# blinkers.net
KiCad netlist of a schematic drawn in Altium Designer
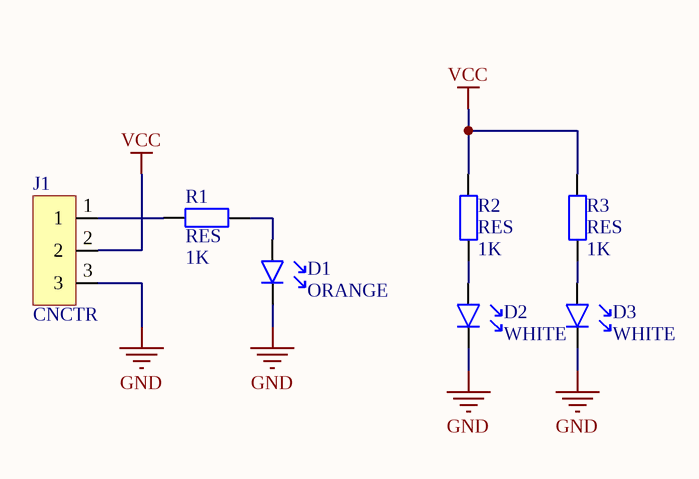
[diagram p0: blinkers.SchDoc]

(export (version "E")
  (design (tool "Eeschema 10.0.6"))
  (components
    (comp (ref "D1") (value "ORANGE") (footprint "RESC1608X06M") (libsource (lib "std") (part "LED")))
    (comp (ref "D2") (value "WHITE") (footprint "RESC1608X06M") (libsource (lib "std") (part "LED")))
    (comp (ref "D3") (value "WHITE") (footprint "RESC1608X06M") (libsource (lib "std") (part "LED")))
    (comp (ref "J1")
      (value "CNCTR")
      (footprint "CNCTR_1X3")
      (description "3pin connector")
      (libsource (lib "std") (part "Connector"))
    )
    (comp (ref "R1")
      (value "RES")
      (footprint "RESC1608X06M")
      (description "Resistor")
      (fields (field (name "ALTIUM_VALUE") "1K") (field (name "PUBLISHER") "Altium Limited"))
      (libsource (lib "") (part "RES_1"))
    )
    (comp (ref "R2")
      (value "RES")
      (footprint "RESC1608X06M")
      (description "Resistor")
      (fields (field (name "ALTIUM_VALUE") "1K") (field (name "PUBLISHER") "Altium Limited"))
      (libsource (lib "std") (part "RES"))
    )
    (comp (ref "R3")
      (value "RES")
      (footprint "RESC1608X06M")
      (description "Resistor")
      (fields (field (name "ALTIUM_VALUE") "1K") (field (name "PUBLISHER") "Altium Limited"))
      (libsource (lib "std") (part "RES"))
    )
  )
  (nets
    (net (code "1") (name "GND") (class "Default")
      (node (ref "D1") (pin "2") (pinfunction "K_2") (pintype "passive"))
      (node (ref "D2") (pin "2") (pinfunction "K_2") (pintype "passive"))
      (node (ref "D3") (pin "2") (pinfunction "K_2") (pintype "passive"))
      (node (ref "J1") (pin "3") (pinfunction "3_3") (pintype "passive"))
    )
    (net (code "2") (name "Net-(D1-A1)") (class "Default")
      (node (ref "D1") (pin "1") (pinfunction "A1_1") (pintype "passive"))
      (node (ref "R1") (pin "2") (pinfunction "2_2") (pintype "passive"))
    )
    (net (code "3") (name "Net-(D2-A1)") (class "Default")
      (node (ref "D2") (pin "1") (pinfunction "A1_1") (pintype "passive"))
      (node (ref "R2") (pin "1") (pinfunction "1_1") (pintype "passive"))
    )
    (net (code "4") (name "Net-(D3-A1)") (class "Default")
      (node (ref "D3") (pin "1") (pinfunction "A1_1") (pintype "passive"))
      (node (ref "R3") (pin "1") (pinfunction "1_1") (pintype "passive"))
    )
    (net (code "5") (name "Net-(J1-Pad1)") (class "Default")
      (node (ref "J1") (pin "1") (pinfunction "1_1") (pintype "passive"))
      (node (ref "R1") (pin "1") (pinfunction "1_1") (pintype "passive"))
    )
    (net (code "6") (name "VCC") (class "Default")
      (node (ref "J1") (pin "2") (pinfunction "2_2") (pintype "passive"))
      (node (ref "R2") (pin "2") (pinfunction "2_2") (pintype "passive"))
      (node (ref "R3") (pin "2") (pinfunction "2_2") (pintype "passive"))
    )
  )
)
